# SSTuino_Evo.net
KiCad netlist of a schematic drawn in EAGLE
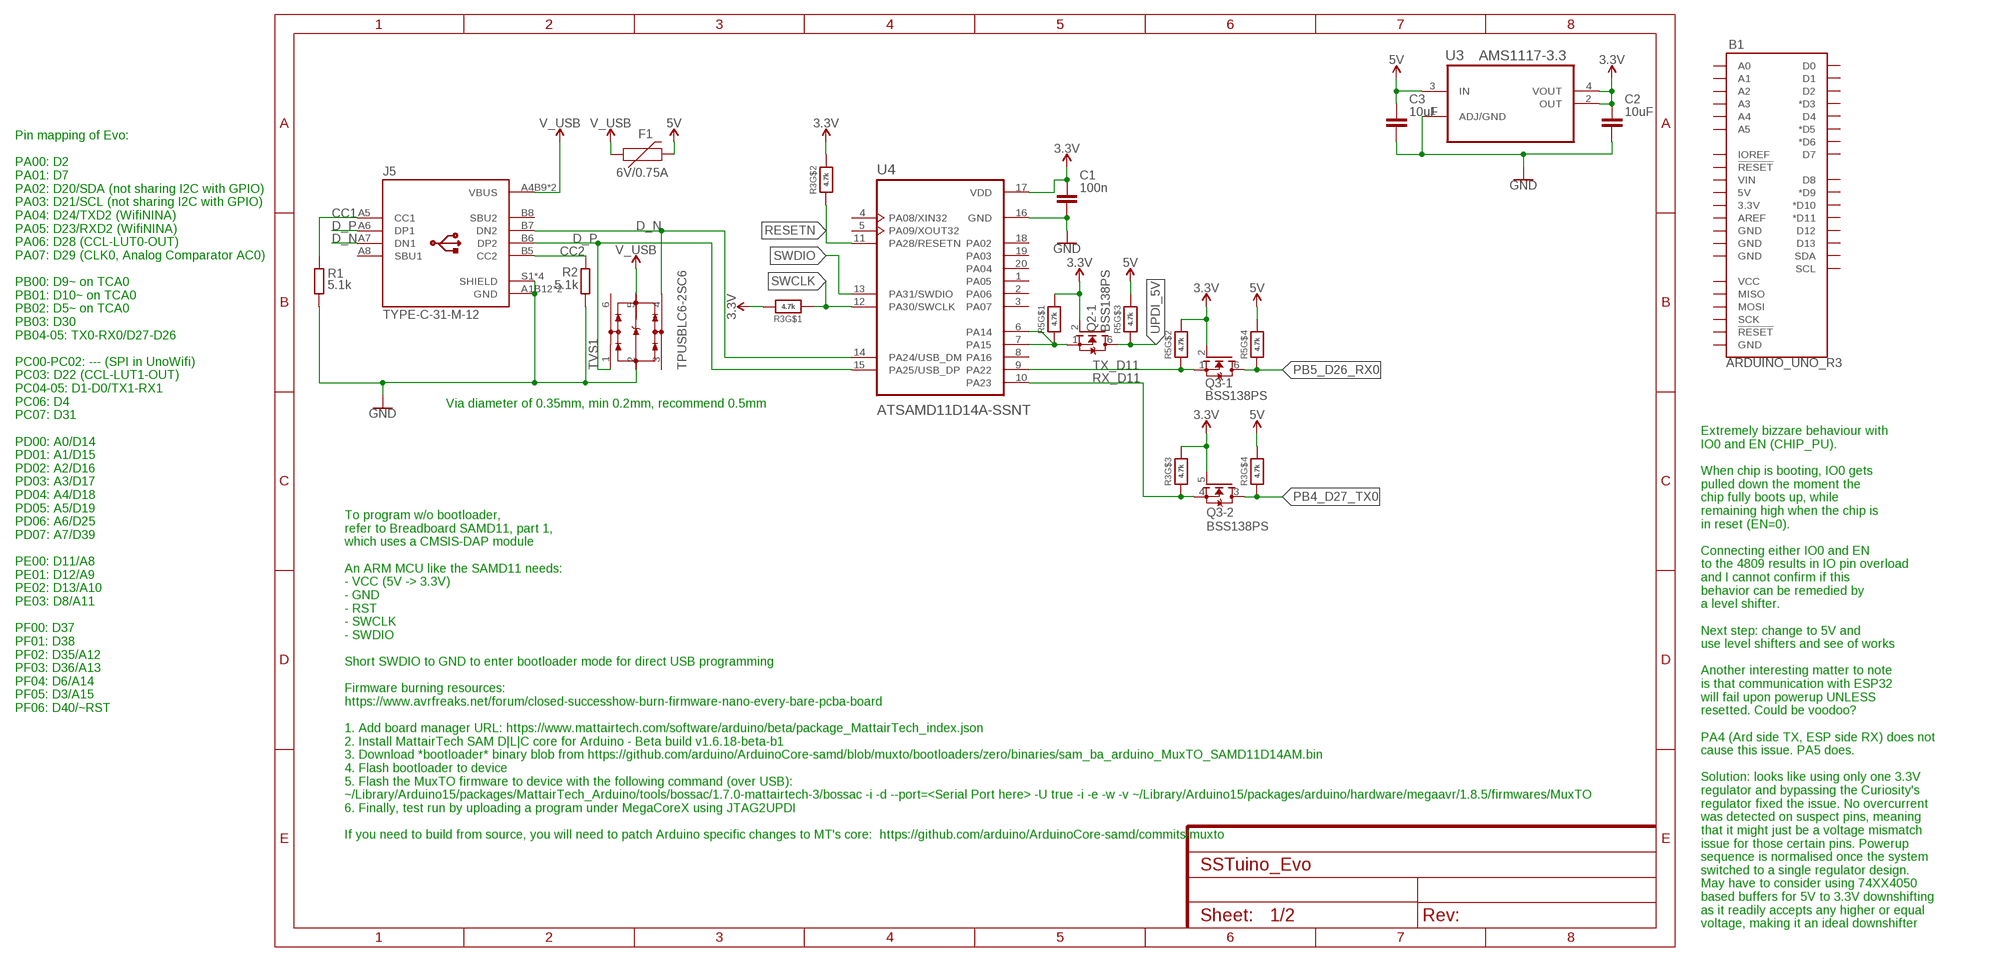
[diagram p0: schematic, sheet 1]
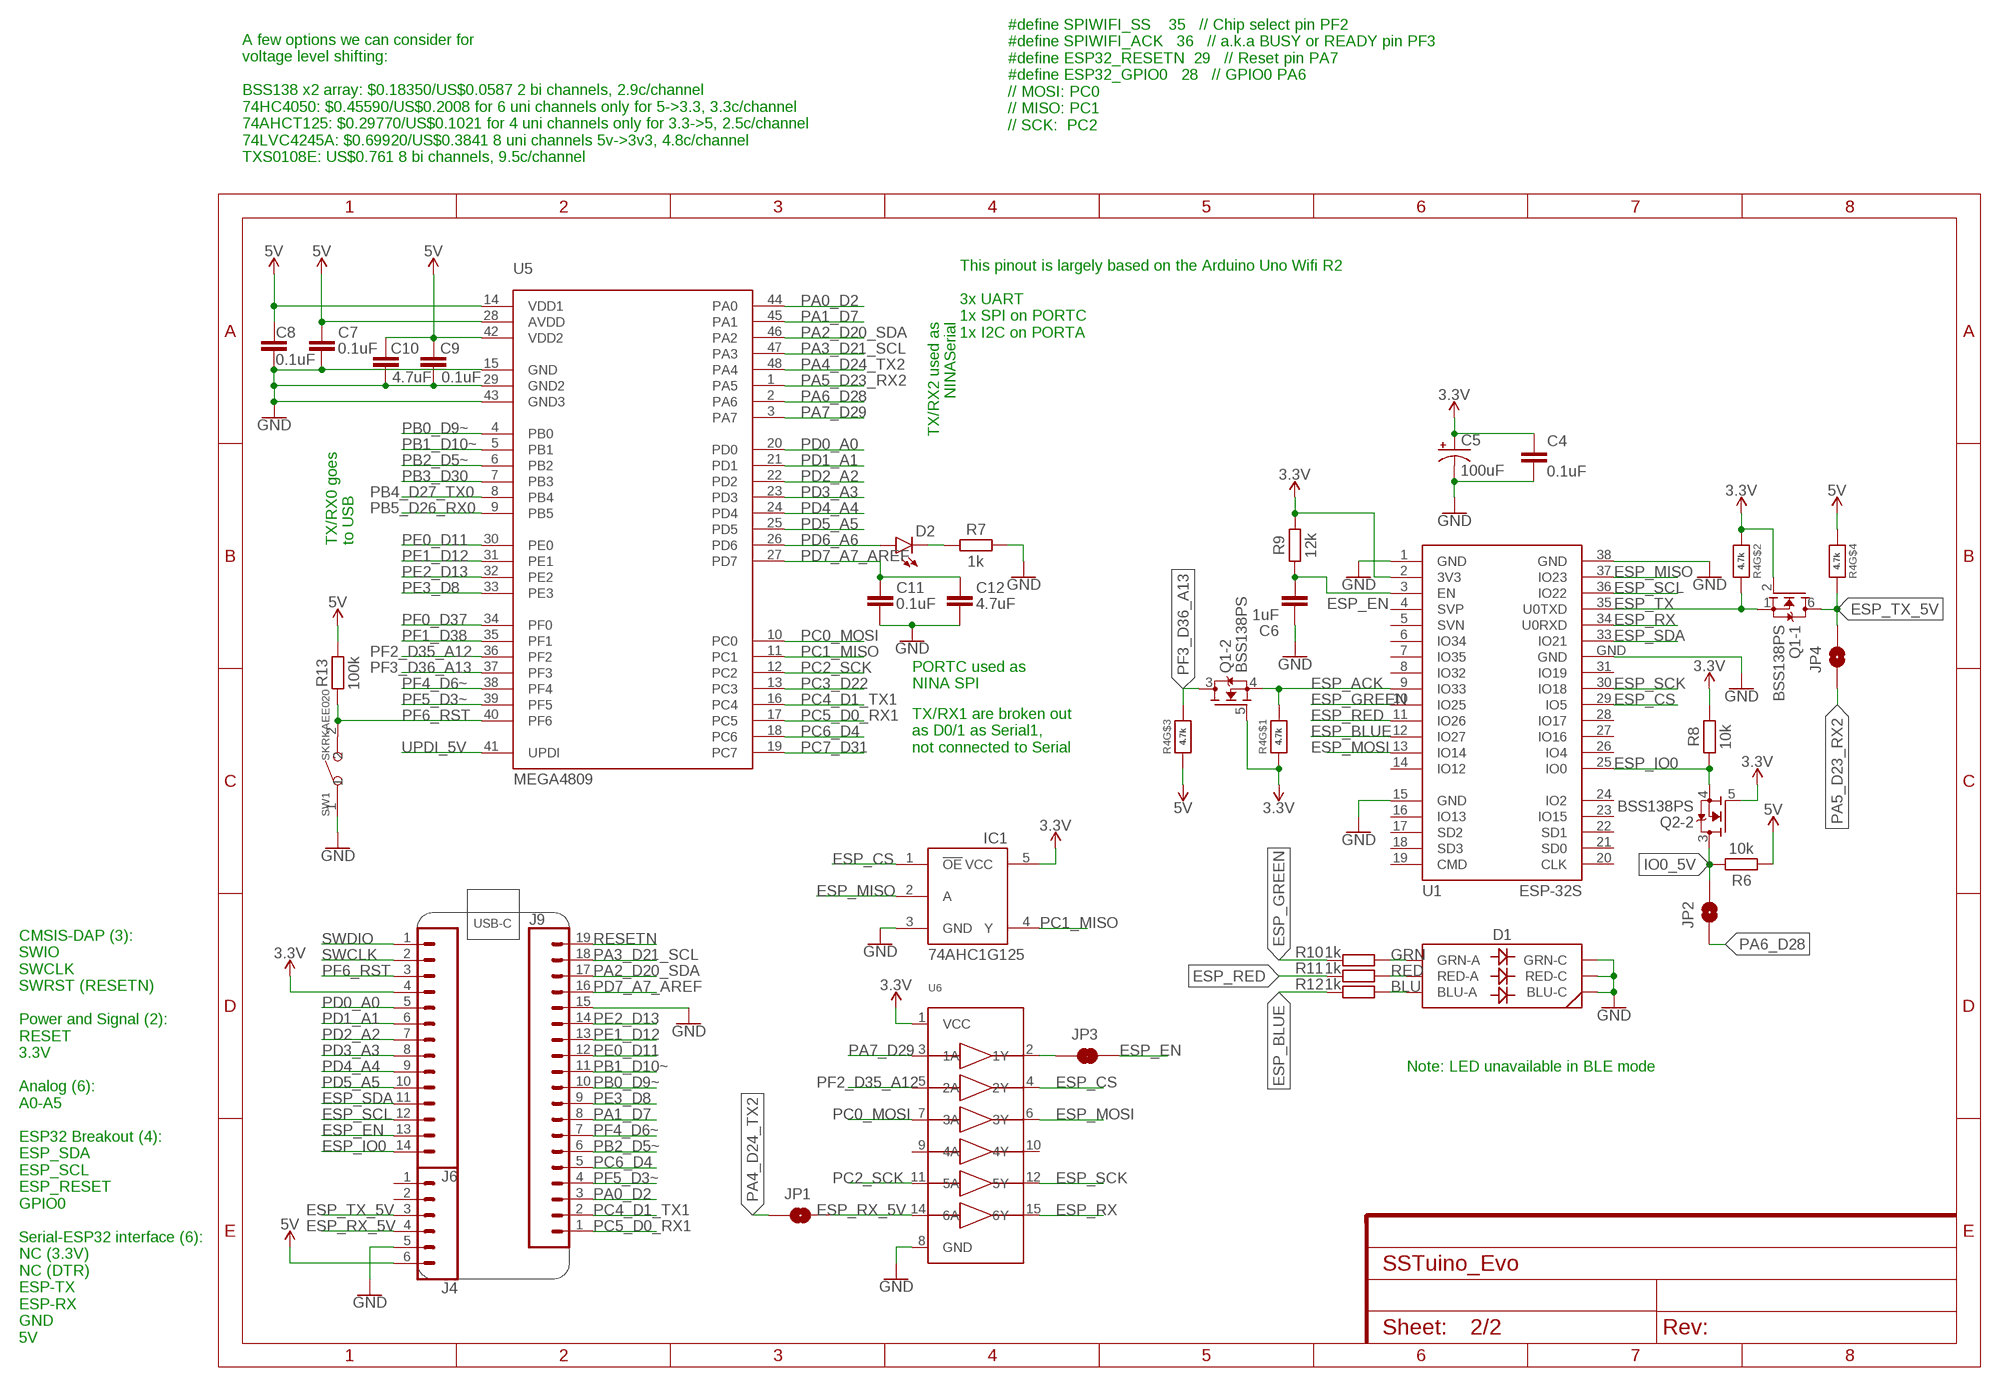
[diagram p1: schematic, sheet 2]

(export (version "E")
  (design (tool "Eeschema 10.0.6"))
  (components
    (comp (ref "B1")
      (value "ARDUINO_UNO_R3")
      (footprint "eagle-import:ARDUINO_R3")
      (libsource (lib "eagle-import") (part "ARDUINO_UNO_R3"))
    )
    (comp (ref "C1")
      (value "100n")
      (footprint "eagle-import:CAPC1005X60")
      (libsource (lib "eagle-import") (part "CCHIP-0402(1005-METRIC)_"))
    )
    (comp (ref "C2")
      (value "10uF")
      (footprint "eagle-import:CAPC1608X85")
      (libsource (lib "eagle-import") (part "CCHIP-0603(1608-METRIC)_"))
    )
    (comp (ref "C3")
      (value "10uF")
      (footprint "eagle-import:CAPC1608X85")
      (libsource (lib "eagle-import") (part "CCHIP-0603(1608-METRIC)_"))
    )
    (comp (ref "F1")
      (value "6V/0.75A")
      (footprint "eagle-import:1206")
      (fields (field (name "LCSC_PART") "C99563"))
      (libsource (lib "eagle-import") (part "PPTC_THREE-QUARTER-AMP"))
    )
    (comp (ref "J5")
      (value "TYPE-C-31-M-12")
      (footprint "eagle-import:HRO_TYPE-C-31-M-12")
      (fields (field (name "MF") "HRO Electronics Co., Ltd.") (field (name "LCSC_PART") "C165948"))
      (libsource (lib "eagle-import") (part "TYPE-C-31-M-12"))
    )
    (comp (ref "Q2")
      (value "BSS138PS")
      (footprint "eagle-import:ARDUINO-TRANSISTORS_SOT363")
      (fields (field (name "MANUFACTURER") "NXP") (field (name "LCSC_PART") "C193381"))
      (libsource (lib "eagle-import") (part "BSS138PS"))
    )
    (comp (ref "Q3")
      (value "BSS138PS")
      (footprint "eagle-import:ARDUINO-TRANSISTORS_SOT363")
      (fields (field (name "MANUFACTURER") "NXP") (field (name "LCSC_PART") "C193381"))
      (libsource (lib "eagle-import") (part "BSS138PS"))
    )
    (comp (ref "R1")
      (value "5.1k")
      (footprint "eagle-import:RESC1005X40")
      (libsource (lib "eagle-import") (part "RCHIP-0402(1005-METRIC)_"))
    )
    (comp (ref "R2")
      (value "5.1k")
      (footprint "eagle-import:RESC1005X40")
      (libsource (lib "eagle-import") (part "RCHIP-0402(1005-METRIC)_"))
    )
    (comp (ref "R3")
      (value "4.7k")
      (footprint "eagle-import:RESPACK_4X0402")
      (fields (field (name "LCSC_PART") "C1980"))
      (libsource (lib "eagle-import") (part "RESISTOR_4PACK0402"))
    )
    (comp (ref "R5")
      (value "4.7k")
      (footprint "eagle-import:RESPACK_4X0402")
      (fields (field (name "LCSC_PART") "C1980"))
      (libsource (lib "eagle-import") (part "RESISTOR_4PACK0402"))
    )
    (comp (ref "TVS1")
      (value "TPUSBLC6-2SC6")
      (footprint "eagle-import:SOT95P280X110-6N")
      (fields (field (name "LCSC_PART") "C558442"))
      (libsource (lib "eagle-import") (part "TPUSBLC6-2SC6"))
    )
    (comp (ref "U3")
      (value "AMS1117-3.3")
      (footprint "eagle-import:SOT230P696X180-4N")
      (fields (field (name "MPN") "LM1117MP-3.3") (field (name "LCSC_PART") "C6186"))
      (libsource (lib "eagle-import") (part "LM1117MP-3.3"))
    )
    (comp (ref "U4")
      (value "ATSAMD11D14A-SSNT")
      (footprint "eagle-import:SOIC127P1030X265-20N")
      (fields (field (name "MF") "Microchip") (field (name "LCSC_PART") "C2053599"))
      (libsource (lib "eagle-import") (part "ATSAMD11D14A-SSNT"))
    )
    (comp (ref "C4")
      (value "0.1uF")
      (footprint "eagle-import:CAPC1005X60")
      (libsource (lib "eagle-import") (part "CCHIP-0402(1005-METRIC)_"))
    )
    (comp (ref "C5")
      (value "100uF")
      (footprint "eagle-import:CAPMP3216X180N")
      (libsource (lib "eagle-import") (part "C-POL-USTANTALUM-1206(3216-METRIC)_"))
    )
    (comp (ref "C6")
      (value "1uF")
      (footprint "eagle-import:CAPC1005X60")
      (libsource (lib "eagle-import") (part "CCHIP-0402(1005-METRIC)_"))
    )
    (comp (ref "C7")
      (value "0.1uF")
      (footprint "eagle-import:CAPC1005X60")
      (libsource (lib "eagle-import") (part "CCHIP-0402(1005-METRIC)_"))
    )
    (comp (ref "C8")
      (value "0.1uF")
      (footprint "eagle-import:CAPC1005X60")
      (libsource (lib "eagle-import") (part "CCHIP-0402(1005-METRIC)_"))
    )
    (comp (ref "C9")
      (value "0.1uF")
      (footprint "eagle-import:CAPC1005X60")
      (libsource (lib "eagle-import") (part "CCHIP-0402(1005-METRIC)_"))
    )
    (comp (ref "C10")
      (value "4.7uF")
      (footprint "eagle-import:CAPC1005X60")
      (libsource (lib "eagle-import") (part "CCHIP-0402(1005-METRIC)_"))
    )
    (comp (ref "C11")
      (value "0.1uF")
      (footprint "eagle-import:CAPC1005X60")
      (libsource (lib "eagle-import") (part "CCHIP-0402(1005-METRIC)_"))
    )
    (comp (ref "C12")
      (value "4.7uF")
      (footprint "eagle-import:CAPC1005X60")
      (libsource (lib "eagle-import") (part "CCHIP-0402(1005-METRIC)_"))
    )
    (comp (ref "D1")
      (value "LED-RGBTC5050RGBF08")
      (footprint "eagle-import:LED-TRICOLOR-5050")
      (libsource (lib "eagle-import") (part "LED-RGBTC5050RGBF08"))
    )
    (comp (ref "D2")
      (value "LED0603")
      (footprint "eagle-import:LED-0603")
      (libsource (lib "eagle-import") (part "LED0603"))
    )
    (comp (ref "IC1")
      (value "74AHC1G125")
      (footprint "eagle-import:SOT23-5L")
      (fields (field (name "LCSC_PART") "C124295"))
      (libsource (lib "eagle-import") (part "74AHC1G125"))
    )
    (comp (ref "J4")
      (value "CONN_06NO_SILK_FEMALE_PTH")
      (footprint "eagle-import:1X06_NO_SILK")
      (libsource (lib "eagle-import") (part "CONN_06NO_SILK_FEMALE_PTH"))
    )
    (comp (ref "J6")
      (value "CONN_14NO_SILK")
      (footprint "eagle-import:1X14_NO_SILK")
      (libsource (lib "eagle-import") (part "CONN_14NO_SILK"))
    )
    (comp (ref "J9")
      (value "CONN_191X19_NO_SILK")
      (footprint "eagle-import:1X19_NO_SILK")
      (libsource (lib "eagle-import") (part "CONN_191X19_NO_SILK"))
    )
    (comp (ref "JP1")
      (value "JUMPER-SMT_2_NO_SILK")
      (footprint "eagle-import:SMT-JUMPER_2_NO_SILK")
      (libsource (lib "eagle-import") (part "JUMPER-SMT_2_NO_SILK"))
    )
    (comp (ref "JP2")
      (value "JUMPER-SMT_2_NO_SILK")
      (footprint "eagle-import:SMT-JUMPER_2_NO_SILK")
      (libsource (lib "eagle-import") (part "JUMPER-SMT_2_NO_SILK"))
    )
    (comp (ref "JP3")
      (value "JUMPER-SMT_2_NC_TRACE_SILK")
      (footprint "eagle-import:SMT-JUMPER_2_NC_TRACE_SILK")
      (libsource (lib "eagle-import") (part "JUMPER-SMT_2_NC_TRACE_SILK"))
    )
    (comp (ref "JP4")
      (value "JUMPER-SMT_2_NO_SILK")
      (footprint "eagle-import:SMT-JUMPER_2_NO_SILK")
      (libsource (lib "eagle-import") (part "JUMPER-SMT_2_NO_SILK"))
    )
    (comp (ref "Q1")
      (value "BSS138PS")
      (footprint "eagle-import:ARDUINO-TRANSISTORS_SOT363")
      (fields (field (name "MANUFACTURER") "NXP") (field (name "LCSC_PART") "C193381"))
      (libsource (lib "eagle-import") (part "BSS138PS"))
    )
    (comp (ref "R4")
      (value "4.7k")
      (footprint "eagle-import:RESPACK_4X0402")
      (fields (field (name "LCSC_PART") "C1980"))
      (libsource (lib "eagle-import") (part "RESISTOR_4PACK0402"))
    )
    (comp (ref "R6")
      (value "10k")
      (footprint "eagle-import:RESC1005X40")
      (libsource (lib "eagle-import") (part "RCHIP-0402(1005-METRIC)_"))
    )
    (comp (ref "R7")
      (value "1k")
      (footprint "eagle-import:RESC1005X40")
      (libsource (lib "eagle-import") (part "RCHIP-0402(1005-METRIC)_"))
    )
    (comp (ref "R8")
      (value "10k")
      (footprint "eagle-import:RESC1005X40")
      (libsource (lib "eagle-import") (part "RCHIP-0402(1005-METRIC)_"))
    )
    (comp (ref "R9")
      (value "12k")
      (footprint "eagle-import:RESC1005X40")
      (libsource (lib "eagle-import") (part "RCHIP-0402(1005-METRIC)_"))
    )
    (comp (ref "R10")
      (value "1k")
      (footprint "eagle-import:RESC1005X40")
      (libsource (lib "eagle-import") (part "RCHIP-0402(1005-METRIC)_"))
    )
    (comp (ref "R11")
      (value "1k")
      (footprint "eagle-import:RESC1005X40")
      (libsource (lib "eagle-import") (part "RCHIP-0402(1005-METRIC)_"))
    )
    (comp (ref "R12")
      (value "1k")
      (footprint "eagle-import:RESC1005X40")
      (libsource (lib "eagle-import") (part "RCHIP-0402(1005-METRIC)_"))
    )
    (comp (ref "R13")
      (value "100k")
      (footprint "eagle-import:RESC1005X40")
      (libsource (lib "eagle-import") (part "RCHIP-0402(1005-METRIC)_"))
    )
    (comp (ref "SW1")
      (value "SKRKAEE020")
      (footprint "eagle-import:SW2-2.6-3.9X2.9X1.5+0.4MM")
      (fields (field (name "LCSC_PART") "C115357") (field (name "LCSC_PART_1") "C115357"))
      (libsource (lib "eagle-import") (part "SMD-BUTTON(2P-3.9X2.9X1.5+0.4MM)-SKRKAEE020"))
    )
    (comp (ref "U1")
      (value "ESP-32S")
      (footprint "eagle-import:ESP-32S")
      (libsource (lib "eagle-import") (part "ESP-32S"))
    )
    (comp (ref "U5")
      (value "MEGA4809")
      (footprint "eagle-import:TQFP48")
      (fields (field (name "LCSC_PART") "C189475"))
      (libsource (lib "eagle-import") (part "MEGA4809"))
    )
    (comp (ref "U6")
      (value "74HC4050DTSSOP")
      (footprint "eagle-import:TSSOP16")
      (fields (field (name "LCSC_PART") "C43181"))
      (libsource (lib "eagle-import") (part "74HC4050DTSSOP"))
    )
  )
  (nets
    (net (code "1") (name "3.3V") (class "Default")
      (node (ref "C1") (pin "1") (pinfunction "1_1") (pintype "passive"))
      (node (ref "C2") (pin "1") (pinfunction "1_1") (pintype "passive"))
      (node (ref "C4") (pin "1") (pinfunction "1_1") (pintype "passive"))
      (node (ref "C5") (pin "1") (pinfunction "+_1") (pintype "passive"))
      (node (ref "IC1") (pin "5") (pinfunction "VCC_5") (pintype "power_in"))
      (node (ref "J6") (pin "4") (pinfunction "4_4") (pintype "passive"))
      (node (ref "Q1") (pin "2") (pinfunction "G_2") (pintype "passive"))
      (node (ref "Q1") (pin "5") (pinfunction "G_5") (pintype "passive"))
      (node (ref "Q2") (pin "2") (pinfunction "G_2") (pintype "passive"))
      (node (ref "Q2") (pin "5") (pinfunction "G_5") (pintype "passive"))
      (node (ref "Q3") (pin "2") (pinfunction "G_2") (pintype "passive"))
      (node (ref "Q3") (pin "5") (pinfunction "G_5") (pintype "passive"))
      (node (ref "R3") (pin "6") (pinfunction "2_6") (pintype "passive"))
      (node (ref "R3") (pin "7") (pinfunction "2_7") (pintype "passive"))
      (node (ref "R3") (pin "8") (pinfunction "2_8") (pintype "passive"))
      (node (ref "R4") (pin "1") (pinfunction "1_1") (pintype "passive"))
      (node (ref "R4") (pin "2") (pinfunction "1_2") (pintype "passive"))
      (node (ref "R5") (pin "7") (pinfunction "2_7") (pintype "passive"))
      (node (ref "R5") (pin "8") (pinfunction "2_8") (pintype "passive"))
      (node (ref "R8") (pin "2") (pinfunction "2_2") (pintype "passive"))
      (node (ref "R9") (pin "2") (pinfunction "2_2") (pintype "passive"))
      (node (ref "U1") (pin "2") (pinfunction "3V3_2") (pintype "power_in"))
      (node (ref "U3") (pin "2") (pinfunction "OUT_2") (pintype "output"))
      (node (ref "U3") (pin "4") (pinfunction "VOUT_4") (pintype "output"))
      (node (ref "U4") (pin "17") (pinfunction "VDD_17") (pintype "power_in"))
      (node (ref "U6") (pin "1") (pinfunction "VCC_1") (pintype "bidirectional"))
    )
    (net (code "2") (name "5V") (class "Default")
      (node (ref "C10") (pin "1") (pinfunction "1_1") (pintype "passive"))
      (node (ref "C3") (pin "1") (pinfunction "1_1") (pintype "passive"))
      (node (ref "C7") (pin "1") (pinfunction "1_1") (pintype "passive"))
      (node (ref "C8") (pin "1") (pinfunction "1_1") (pintype "passive"))
      (node (ref "C9") (pin "1") (pinfunction "1_1") (pintype "passive"))
      (node (ref "F1") (pin "2") (pinfunction "2_2") (pintype "bidirectional"))
      (node (ref "J4") (pin "6") (pinfunction "6_6") (pintype "passive"))
      (node (ref "R13") (pin "2") (pinfunction "2_2") (pintype "passive"))
      (node (ref "R3") (pin "5") (pinfunction "2_5") (pintype "passive"))
      (node (ref "R4") (pin "3") (pinfunction "1_3") (pintype "passive"))
      (node (ref "R4") (pin "4") (pinfunction "1_4") (pintype "passive"))
      (node (ref "R5") (pin "5") (pinfunction "2_5") (pintype "passive"))
      (node (ref "R5") (pin "6") (pinfunction "2_6") (pintype "passive"))
      (node (ref "R6") (pin "1") (pinfunction "1_1") (pintype "passive"))
      (node (ref "U3") (pin "3") (pinfunction "IN_3") (pintype "input"))
      (node (ref "U5") (pin "14") (pinfunction "VDD1_14") (pintype "bidirectional"))
      (node (ref "U5") (pin "28") (pinfunction "AVDD_28") (pintype "bidirectional"))
      (node (ref "U5") (pin "42") (pinfunction "VDD2_42") (pintype "bidirectional"))
    )
    (net (code "3") (name "BLU") (class "Default")
      (node (ref "D1") (pin "6") (pinfunction "BLU-A_6") (pintype "bidirectional"))
      (node (ref "R12") (pin "2") (pinfunction "2_2") (pintype "passive"))
    )
    (net (code "4") (name "CC1") (class "Default")
      (node (ref "J5") (pin "A5") (pinfunction "CC1_A5") (pintype "bidirectional"))
      (node (ref "R1") (pin "1") (pinfunction "1_1") (pintype "passive"))
    )
    (net (code "5") (name "CC2") (class "Default")
      (node (ref "J5") (pin "B5") (pinfunction "CC2_B5") (pintype "bidirectional"))
      (node (ref "R2") (pin "2") (pinfunction "2_2") (pintype "passive"))
    )
    (net (code "6") (name "D_N") (class "Default")
      (node (ref "J5") (pin "A7") (pinfunction "DN1_A7") (pintype "bidirectional"))
      (node (ref "J5") (pin "B7") (pinfunction "DN2_B7") (pintype "bidirectional"))
      (node (ref "TVS1") (pin "4") (pinfunction "IO3_4") (pintype "passive"))
      (node (ref "U4") (pin "14") (pinfunction "PA24/USB_DM_14") (pintype "bidirectional"))
    )
    (net (code "7") (name "D_P") (class "Default")
      (node (ref "J5") (pin "A6") (pinfunction "DP1_A6") (pintype "bidirectional"))
      (node (ref "J5") (pin "B6") (pinfunction "DP2_B6") (pintype "bidirectional"))
      (node (ref "TVS1") (pin "1") (pinfunction "IO1_1") (pintype "passive"))
      (node (ref "U4") (pin "15") (pinfunction "PA25/USB_DP_15") (pintype "bidirectional"))
    )
    (net (code "8") (name "ESP_ACK") (class "Default")
      (node (ref "Q1") (pin "4") (pinfunction "S_4") (pintype "passive"))
      (node (ref "R4") (pin "8") (pinfunction "2_8") (pintype "passive"))
      (node (ref "U1") (pin "9") (pinfunction "IO33_9") (pintype "bidirectional"))
    )
    (net (code "9") (name "ESP_BLUE") (class "Default")
      (node (ref "R12") (pin "1") (pinfunction "1_1") (pintype "passive"))
      (node (ref "U1") (pin "12") (pinfunction "IO27_12") (pintype "bidirectional"))
    )
    (net (code "10") (name "ESP_CS") (class "Default")
      (node (ref "IC1") (pin "1") (pinfunction "~{OE}_1") (pintype "input"))
      (node (ref "U1") (pin "29") (pinfunction "IO5_29") (pintype "bidirectional"))
      (node (ref "U6") (pin "4") (pinfunction "2Y_4") (pintype "bidirectional"))
    )
    (net (code "11") (name "ESP_EN") (class "Default")
      (node (ref "C6") (pin "2") (pinfunction "2_2") (pintype "passive"))
      (node (ref "J6") (pin "13") (pinfunction "13_13") (pintype "passive"))
      (node (ref "JP3") (pin "2") (pinfunction "2_2") (pintype "passive"))
      (node (ref "R9") (pin "1") (pinfunction "1_1") (pintype "passive"))
      (node (ref "U1") (pin "3") (pinfunction "EN_3") (pintype "input"))
    )
    (net (code "12") (name "ESP_GREEN") (class "Default")
      (node (ref "R10") (pin "1") (pinfunction "1_1") (pintype "passive"))
      (node (ref "U1") (pin "10") (pinfunction "IO25_10") (pintype "bidirectional"))
    )
    (net (code "13") (name "ESP_IO0") (class "Default")
      (node (ref "J6") (pin "14") (pinfunction "14_14") (pintype "passive"))
      (node (ref "Q2") (pin "4") (pinfunction "S_4") (pintype "passive"))
      (node (ref "R8") (pin "1") (pinfunction "1_1") (pintype "passive"))
      (node (ref "U1") (pin "25") (pinfunction "IO0_25") (pintype "bidirectional"))
    )
    (net (code "14") (name "ESP_MISO") (class "Default")
      (node (ref "IC1") (pin "2") (pinfunction "A_2") (pintype "input"))
      (node (ref "U1") (pin "37") (pinfunction "IO23_37") (pintype "bidirectional"))
    )
    (net (code "15") (name "ESP_MOSI") (class "Default")
      (node (ref "U1") (pin "13") (pinfunction "IO14_13") (pintype "bidirectional"))
      (node (ref "U6") (pin "6") (pinfunction "3Y_6") (pintype "bidirectional"))
    )
    (net (code "16") (name "ESP_RED") (class "Default")
      (node (ref "R11") (pin "1") (pinfunction "1_1") (pintype "passive"))
      (node (ref "U1") (pin "11") (pinfunction "IO26_11") (pintype "bidirectional"))
    )
    (net (code "17") (name "ESP_RX") (class "Default")
      (node (ref "U1") (pin "34") (pinfunction "U0RXD_34") (pintype "bidirectional"))
      (node (ref "U6") (pin "15") (pinfunction "6Y_15") (pintype "bidirectional"))
    )
    (net (code "18") (name "ESP_RX_5V") (class "Default")
      (node (ref "J4") (pin "4") (pinfunction "4_4") (pintype "passive"))
      (node (ref "JP1") (pin "2") (pinfunction "2_2") (pintype "passive"))
      (node (ref "U6") (pin "14") (pinfunction "6A_14") (pintype "bidirectional"))
    )
    (net (code "19") (name "ESP_SCK") (class "Default")
      (node (ref "U1") (pin "30") (pinfunction "IO18_30") (pintype "bidirectional"))
      (node (ref "U6") (pin "12") (pinfunction "5Y_12") (pintype "bidirectional"))
    )
    (net (code "20") (name "ESP_SCL") (class "Default")
      (node (ref "J6") (pin "12") (pinfunction "12_12") (pintype "passive"))
      (node (ref "U1") (pin "36") (pinfunction "IO22_36") (pintype "bidirectional"))
    )
    (net (code "21") (name "ESP_SDA") (class "Default")
      (node (ref "J6") (pin "11") (pinfunction "11_11") (pintype "passive"))
      (node (ref "U1") (pin "33") (pinfunction "IO21_33") (pintype "bidirectional"))
    )
    (net (code "22") (name "ESP_TX") (class "Default")
      (node (ref "Q1") (pin "1") (pinfunction "S_1") (pintype "passive"))
      (node (ref "R4") (pin "7") (pinfunction "2_7") (pintype "passive"))
      (node (ref "U1") (pin "35") (pinfunction "U0TXD_35") (pintype "bidirectional"))
    )
    (net (code "23") (name "ESP_TX_5V") (class "Default")
      (node (ref "J4") (pin "3") (pinfunction "3_3") (pintype "passive"))
      (node (ref "JP4") (pin "2") (pinfunction "2_2") (pintype "passive"))
      (node (ref "Q1") (pin "6") (pinfunction "D_6") (pintype "passive"))
      (node (ref "R4") (pin "5") (pinfunction "2_5") (pintype "passive"))
    )
    (net (code "24") (name "GND") (class "Default")
      (node (ref "C1") (pin "2") (pinfunction "2_2") (pintype "passive"))
      (node (ref "C10") (pin "2") (pinfunction "2_2") (pintype "passive"))
      (node (ref "C11") (pin "2") (pinfunction "2_2") (pintype "passive"))
      (node (ref "C12") (pin "2") (pinfunction "2_2") (pintype "passive"))
      (node (ref "C2") (pin "2") (pinfunction "2_2") (pintype "passive"))
      (node (ref "C3") (pin "2") (pinfunction "2_2") (pintype "passive"))
      (node (ref "C4") (pin "2") (pinfunction "2_2") (pintype "passive"))
      (node (ref "C5") (pin "2") (pinfunction "-_2") (pintype "passive"))
      (node (ref "C6") (pin "1") (pinfunction "1_1") (pintype "passive"))
      (node (ref "C7") (pin "2") (pinfunction "2_2") (pintype "passive"))
      (node (ref "C8") (pin "2") (pinfunction "2_2") (pintype "passive"))
      (node (ref "C9") (pin "2") (pinfunction "2_2") (pintype "passive"))
      (node (ref "D1") (pin "1") (pinfunction "BLU-C_1") (pintype "bidirectional"))
      (node (ref "D1") (pin "2") (pinfunction "RED-C_2") (pintype "bidirectional"))
      (node (ref "D1") (pin "3") (pinfunction "GRN-C_3") (pintype "bidirectional"))
      (node (ref "IC1") (pin "3") (pinfunction "GND_3") (pintype "power_in"))
      (node (ref "J4") (pin "5") (pinfunction "5_5") (pintype "passive"))
      (node (ref "J5") (pin "A1B12") (pinfunction "GND_A1B12") (pintype "power_in"))
      (node (ref "J5") (pin "B1A12") (pinfunction "GND_B1A12") (pintype "power_in"))
      (node (ref "J5") (pin "S1") (pinfunction "SHIELD_S1") (pintype "passive"))
      (node (ref "J5") (pin "S2") (pinfunction "SHIELD_S2") (pintype "passive"))
      (node (ref "J5") (pin "S3") (pinfunction "SHIELD_S3") (pintype "passive"))
      (node (ref "J5") (pin "S4") (pinfunction "SHIELD_S4") (pintype "passive"))
      (node (ref "J9") (pin "15") (pinfunction "15_15") (pintype "passive"))
      (node (ref "R1") (pin "2") (pinfunction "2_2") (pintype "passive"))
      (node (ref "R2") (pin "1") (pinfunction "1_1") (pintype "passive"))
      (node (ref "R7") (pin "2") (pinfunction "2_2") (pintype "passive"))
      (node (ref "SW1") (pin "1") (pinfunction "1_1") (pintype "bidirectional"))
      (node (ref "TVS1") (pin "2") (pinfunction "VSS_2") (pintype "power_in"))
      (node (ref "U1") (pin "1") (pinfunction "GND_1") (pintype "power_in"))
      (node (ref "U1") (pin "15") (pinfunction "GND_15") (pintype "power_in"))
      (node (ref "U1") (pin "38") (pinfunction "GND_38") (pintype "power_in"))
      (node (ref "U1") (pin "GND") (pinfunction "GND_GND") (pintype "power_in"))
      (node (ref "U3") (pin "1") (pinfunction "ADJ/GND_1") (pintype "passive"))
      (node (ref "U4") (pin "16") (pinfunction "GND_16") (pintype "power_in"))
      (node (ref "U5") (pin "15") (pinfunction "GND_15") (pintype "bidirectional"))
      (node (ref "U5") (pin "29") (pinfunction "GND2_29") (pintype "bidirectional"))
      (node (ref "U5") (pin "43") (pinfunction "GND3_43") (pintype "bidirectional"))
      (node (ref "U6") (pin "8") (pinfunction "GND_8") (pintype "bidirectional"))
    )
    (net (code "25") (name "GRN") (class "Default")
      (node (ref "D1") (pin "4") (pinfunction "GRN-A_4") (pintype "bidirectional"))
      (node (ref "R10") (pin "2") (pinfunction "2_2") (pintype "passive"))
    )
    (net (code "26") (name "IO0_5V") (class "Default")
      (node (ref "JP2") (pin "2") (pinfunction "2_2") (pintype "passive"))
      (node (ref "Q2") (pin "3") (pinfunction "D_3") (pintype "passive"))
      (node (ref "R6") (pin "2") (pinfunction "2_2") (pintype "passive"))
    )
    (net (code "27") (name "Net-(D2-PadC)") (class "Default")
      (node (ref "D2") (pin "C") (pinfunction "C_C") (pintype "passive"))
      (node (ref "R7") (pin "1") (pinfunction "1_1") (pintype "passive"))
    )
    (net (code "28") (name "Net-(Q2A-S)") (class "Default")
      (node (ref "Q2") (pin "1") (pinfunction "S_1") (pintype "passive"))
      (node (ref "R5") (pin "1") (pinfunction "1_1") (pintype "passive"))
      (node (ref "U4") (pin "6") (pinfunction "PA14_6") (pintype "bidirectional"))
      (node (ref "U4") (pin "7") (pinfunction "PA15_7") (pintype "bidirectional"))
    )
    (net (code "29") (name "Net-(U6-1Y)") (class "Default")
      (node (ref "JP3") (pin "1") (pinfunction "1_1") (pintype "passive"))
      (node (ref "U6") (pin "2") (pinfunction "1Y_2") (pintype "bidirectional"))
    )
    (net (code "30") (name "PA0_D2") (class "Default")
      (node (ref "J9") (pin "3") (pinfunction "3_3") (pintype "passive"))
      (node (ref "U5") (pin "44") (pinfunction "PA0_44") (pintype "bidirectional"))
    )
    (net (code "31") (name "PA1_D7") (class "Default")
      (node (ref "J9") (pin "8") (pinfunction "8_8") (pintype "passive"))
      (node (ref "U5") (pin "45") (pinfunction "PA1_45") (pintype "bidirectional"))
    )
    (net (code "32") (name "PA2_D20_SDA") (class "Default")
      (node (ref "J9") (pin "17") (pinfunction "17_17") (pintype "passive"))
      (node (ref "U5") (pin "46") (pinfunction "PA2_46") (pintype "bidirectional"))
    )
    (net (code "33") (name "PA3_D21_SCL") (class "Default")
      (node (ref "J9") (pin "18") (pinfunction "18_18") (pintype "passive"))
      (node (ref "U5") (pin "47") (pinfunction "PA3_47") (pintype "bidirectional"))
    )
    (net (code "34") (name "PA4_D24_TX2") (class "Default")
      (node (ref "JP1") (pin "1") (pinfunction "1_1") (pintype "passive"))
      (node (ref "U5") (pin "48") (pinfunction "PA4_48") (pintype "bidirectional"))
    )
    (net (code "35") (name "PA5_D23_RX2") (class "Default")
      (node (ref "JP4") (pin "1") (pinfunction "1_1") (pintype "passive"))
      (node (ref "U5") (pin "1") (pinfunction "PA5_1") (pintype "bidirectional"))
    )
    (net (code "36") (name "PA6_D28") (class "Default")
      (node (ref "JP2") (pin "1") (pinfunction "1_1") (pintype "passive"))
      (node (ref "U5") (pin "2") (pinfunction "PA6_2") (pintype "bidirectional"))
    )
    (net (code "37") (name "PA7_D29") (class "Default")
      (node (ref "U5") (pin "3") (pinfunction "PA7_3") (pintype "bidirectional"))
      (node (ref "U6") (pin "3") (pinfunction "1A_3") (pintype "bidirectional"))
    )
    (net (code "38") (name "PB0_D9~{}") (class "Default")
      (node (ref "J9") (pin "10") (pinfunction "10_10") (pintype "passive"))
      (node (ref "U5") (pin "4") (pinfunction "PB0_4") (pintype "bidirectional"))
    )
    (net (code "39") (name "PB1_D10~{}") (class "Default")
      (node (ref "J9") (pin "11") (pinfunction "11_11") (pintype "passive"))
      (node (ref "U5") (pin "5") (pinfunction "PB1_5") (pintype "bidirectional"))
    )
    (net (code "40") (name "PB2_D5~{}") (class "Default")
      (node (ref "J9") (pin "6") (pinfunction "6_6") (pintype "passive"))
      (node (ref "U5") (pin "6") (pinfunction "PB2_6") (pintype "bidirectional"))
    )
    (net (code "41") (name "PB3_D30") (class "Default")
      (node (ref "U5") (pin "7") (pinfunction "PB3_7") (pintype "bidirectional"))
    )
    (net (code "42") (name "PB4_D27_TX0") (class "Default")
      (node (ref "Q3") (pin "3") (pinfunction "D_3") (pintype "passive"))
      (node (ref "R3") (pin "4") (pinfunction "1_4") (pintype "passive"))
      (node (ref "U5") (pin "8") (pinfunction "PB4_8") (pintype "bidirectional"))
    )
    (net (code "43") (name "PB5_D26_RX0") (class "Default")
      (node (ref "Q3") (pin "6") (pinfunction "D_6") (pintype "passive"))
      (node (ref "R5") (pin "4") (pinfunction "1_4") (pintype "passive"))
      (node (ref "U5") (pin "9") (pinfunction "PB5_9") (pintype "bidirectional"))
    )
    (net (code "44") (name "PC0_MOSI") (class "Default")
      (node (ref "U5") (pin "10") (pinfunction "PC0_10") (pintype "bidirectional"))
      (node (ref "U6") (pin "7") (pinfunction "3A_7") (pintype "bidirectional"))
    )
    (net (code "45") (name "PC1_MISO") (class "Default")
      (node (ref "IC1") (pin "4") (pinfunction "Y_4") (pintype "output"))
      (node (ref "U5") (pin "11") (pinfunction "PC1_11") (pintype "bidirectional"))
    )
    (net (code "46") (name "PC2_SCK") (class "Default")
      (node (ref "U5") (pin "12") (pinfunction "PC2_12") (pintype "bidirectional"))
      (node (ref "U6") (pin "11") (pinfunction "5A_11") (pintype "bidirectional"))
    )
    (net (code "47") (name "PC3_D22") (class "Default")
      (node (ref "U5") (pin "13") (pinfunction "PC3_13") (pintype "bidirectional"))
    )
    (net (code "48") (name "PC4_D1_TX1") (class "Default")
      (node (ref "J9") (pin "2") (pinfunction "2_2") (pintype "passive"))
      (node (ref "U5") (pin "16") (pinfunction "PC4_16") (pintype "bidirectional"))
    )
    (net (code "49") (name "PC5_D0_RX1") (class "Default")
      (node (ref "J9") (pin "1") (pinfunction "1_1") (pintype "passive"))
      (node (ref "U5") (pin "17") (pinfunction "PC5_17") (pintype "bidirectional"))
    )
    (net (code "50") (name "PC6_D4") (class "Default")
      (node (ref "J9") (pin "5") (pinfunction "5_5") (pintype "passive"))
      (node (ref "U5") (pin "18") (pinfunction "PC6_18") (pintype "bidirectional"))
    )
    (net (code "51") (name "PC7_D31") (class "Default")
      (node (ref "U5") (pin "19") (pinfunction "PC7_19") (pintype "bidirectional"))
    )
    (net (code "52") (name "PD0_A0") (class "Default")
      (node (ref "J6") (pin "5") (pinfunction "5_5") (pintype "passive"))
      (node (ref "U5") (pin "20") (pinfunction "PD0_20") (pintype "bidirectional"))
    )
    (net (code "53") (name "PD1_A1") (class "Default")
      (node (ref "J6") (pin "6") (pinfunction "6_6") (pintype "passive"))
      (node (ref "U5") (pin "21") (pinfunction "PD1_21") (pintype "bidirectional"))
    )
    (net (code "54") (name "PD2_A2") (class "Default")
      (node (ref "J6") (pin "7") (pinfunction "7_7") (pintype "passive"))
      (node (ref "U5") (pin "22") (pinfunction "PD2_22") (pintype "bidirectional"))
    )
    (net (code "55") (name "PD3_A3") (class "Default")
      (node (ref "J6") (pin "8") (pinfunction "8_8") (pintype "passive"))
      (node (ref "U5") (pin "23") (pinfunction "PD3_23") (pintype "bidirectional"))
    )
    (net (code "56") (name "PD4_A4") (class "Default")
      (node (ref "J6") (pin "9") (pinfunction "9_9") (pintype "passive"))
      (node (ref "U5") (pin "24") (pinfunction "PD4_24") (pintype "bidirectional"))
    )
    (net (code "57") (name "PD5_A5") (class "Default")
      (node (ref "J6") (pin "10") (pinfunction "10_10") (pintype "passive"))
      (node (ref "U5") (pin "25") (pinfunction "PD5_25") (pintype "bidirectional"))
    )
    (net (code "58") (name "PD6_A6") (class "Default")
      (node (ref "D2") (pin "A") (pinfunction "A_A") (pintype "passive"))
      (node (ref "U5") (pin "26") (pinfunction "PD6_26") (pintype "bidirectional"))
    )
    (net (code "59") (name "PD7_A7_AREF") (class "Default")
      (node (ref "C11") (pin "1") (pinfunction "1_1") (pintype "passive"))
      (node (ref "C12") (pin "1") (pinfunction "1_1") (pintype "passive"))
      (node (ref "J9") (pin "16") (pinfunction "16_16") (pintype "passive"))
      (node (ref "U5") (pin "27") (pinfunction "PD7_27") (pintype "bidirectional"))
    )
    (net (code "60") (name "PE0_D11") (class "Default")
      (node (ref "J9") (pin "12") (pinfunction "12_12") (pintype "passive"))
      (node (ref "U5") (pin "30") (pinfunction "PE0_30") (pintype "bidirectional"))
    )
    (net (code "61") (name "PE1_D12") (class "Default")
      (node (ref "J9") (pin "13") (pinfunction "13_13") (pintype "passive"))
      (node (ref "U5") (pin "31") (pinfunction "PE1_31") (pintype "bidirectional"))
    )
    (net (code "62") (name "PE2_D13") (class "Default")
      (node (ref "J9") (pin "14") (pinfunction "14_14") (pintype "passive"))
      (node (ref "U5") (pin "32") (pinfunction "PE2_32") (pintype "bidirectional"))
    )
    (net (code "63") (name "PE3_D8") (class "Default")
      (node (ref "J9") (pin "9") (pinfunction "9_9") (pintype "passive"))
      (node (ref "U5") (pin "33") (pinfunction "PE3_33") (pintype "bidirectional"))
    )
    (net (code "64") (name "PF0_D37") (class "Default")
      (node (ref "U5") (pin "34") (pinfunction "PF0_34") (pintype "bidirectional"))
    )
    (net (code "65") (name "PF1_D38") (class "Default")
      (node (ref "U5") (pin "35") (pinfunction "PF1_35") (pintype "bidirectional"))
    )
    (net (code "66") (name "PF2_D35_A12") (class "Default")
      (node (ref "U5") (pin "36") (pinfunction "PF2_36") (pintype "bidirectional"))
      (node (ref "U6") (pin "5") (pinfunction "2A_5") (pintype "bidirectional"))
    )
    (net (code "67") (name "PF3_D36_A13") (class "Default")
      (node (ref "Q1") (pin "3") (pinfunction "D_3") (pintype "passive"))
      (node (ref "R4") (pin "6") (pinfunction "2_6") (pintype "passive"))
      (node (ref "U5") (pin "37") (pinfunction "PF3_37") (pintype "bidirectional"))
    )
    (net (code "68") (name "PF4_D6~{}") (class "Default")
      (node (ref "J9") (pin "7") (pinfunction "7_7") (pintype "passive"))
      (node (ref "U5") (pin "38") (pinfunction "PF4_38") (pintype "bidirectional"))
    )
    (net (code "69") (name "PF5_D3~{}") (class "Default")
      (node (ref "J9") (pin "4") (pinfunction "4_4") (pintype "passive"))
      (node (ref "U5") (pin "39") (pinfunction "PF5_39") (pintype "bidirectional"))
    )
    (net (code "70") (name "PF6_RST") (class "Default")
      (node (ref "J6") (pin "3") (pinfunction "3_3") (pintype "passive"))
      (node (ref "R13") (pin "1") (pinfunction "1_1") (pintype "passive"))
      (node (ref "SW1") (pin "2") (pinfunction "2_2") (pintype "bidirectional"))
      (node (ref "U5") (pin "40") (pinfunction "PF6_40") (pintype "bidirectional"))
    )
    (net (code "71") (name "RED") (class "Default")
      (node (ref "D1") (pin "5") (pinfunction "RED-A_5") (pintype "bidirectional"))
      (node (ref "R11") (pin "2") (pinfunction "2_2") (pintype "passive"))
    )
    (net (code "72") (name "RESETN") (class "Default")
      (node (ref "J9") (pin "19") (pinfunction "19_19") (pintype "passive"))
      (node (ref "R3") (pin "2") (pinfunction "1_2") (pintype "passive"))
      (node (ref "U4") (pin "11") (pinfunction "PA28/RESETN_11") (pintype "input"))
    )
    (net (code "73") (name "RX_D11") (class "Default")
      (node (ref "Q3") (pin "4") (pinfunction "S_4") (pintype "passive"))
      (node (ref "R3") (pin "3") (pinfunction "1_3") (pintype "passive"))
      (node (ref "U4") (pin "10") (pinfunction "PA23_10") (pintype "bidirectional"))
    )
    (net (code "74") (name "SWCLK") (class "Default")
      (node (ref "J6") (pin "2") (pinfunction "2_2") (pintype "passive"))
      (node (ref "R3") (pin "1") (pinfunction "1_1") (pintype "passive"))
      (node (ref "U4") (pin "12") (pinfunction "PA30/SWCLK_12") (pintype "bidirectional"))
    )
    (net (code "75") (name "SWDIO") (class "Default")
      (node (ref "J6") (pin "1") (pinfunction "1_1") (pintype "passive"))
      (node (ref "U4") (pin "13") (pinfunction "PA31/SWDIO_13") (pintype "bidirectional"))
    )
    (net (code "76") (name "TX_D11") (class "Default")
      (node (ref "Q3") (pin "1") (pinfunction "S_1") (pintype "passive"))
      (node (ref "R5") (pin "2") (pinfunction "1_2") (pintype "passive"))
      (node (ref "U4") (pin "9") (pinfunction "PA22_9") (pintype "bidirectional"))
    )
    (net (code "77") (name "UPDI_5V") (class "Default")
      (node (ref "Q2") (pin "6") (pinfunction "D_6") (pintype "passive"))
      (node (ref "R5") (pin "3") (pinfunction "1_3") (pintype "passive"))
      (node (ref "U5") (pin "41") (pinfunction "UPDI_41") (pintype "bidirectional"))
    )
    (net (code "78") (name "V_USB") (class "Default")
      (node (ref "F1") (pin "1") (pinfunction "1_1") (pintype "bidirectional"))
      (node (ref "J5") (pin "A4B9") (pinfunction "VBUS_A4B9") (pintype "power_in"))
      (node (ref "J5") (pin "B4A9") (pinfunction "VBUS_B4A9") (pintype "power_in"))
      (node (ref "TVS1") (pin "5") (pinfunction "VCC_5") (pintype "power_in"))
    )
    (net (code "79") (name "unconnected-(B1-*D3-PadD3)") (class "Default")
      (node (ref "B1") (pin "D3") (pinfunction "*D3_D3") (pintype "bidirectional"))
    )
    (net (code "80") (name "unconnected-(B1-*D5-PadD5)") (class "Default")
      (node (ref "B1") (pin "D5") (pinfunction "*D5_D5") (pintype "bidirectional"))
    )
    (net (code "81") (name "unconnected-(B1-*D6-PadD6)") (class "Default")
      (node (ref "B1") (pin "D6") (pinfunction "*D6_D6") (pintype "bidirectional"))
    )
    (net (code "82") (name "unconnected-(B1-*D9-PadD9)") (class "Default")
      (node (ref "B1") (pin "D9") (pinfunction "*D9_D9") (pintype "bidirectional"))
    )
    (net (code "83") (name "unconnected-(B1-*D10-PadD10)") (class "Default")
      (node (ref "B1") (pin "D10") (pinfunction "*D10_D10") (pintype "bidirectional"))
    )
    (net (code "84") (name "unconnected-(B1-*D11-PadD11)") (class "Default")
      (node (ref "B1") (pin "D11") (pinfunction "*D11_D11") (pintype "bidirectional"))
    )
    (net (code "85") (name "unconnected-(B1-GND-PadGND@1)") (class "Default")
      (node (ref "B1") (pin "GND@1") (pinfunction "GND_GND@1") (pintype "bidirectional"))
    )
    (net (code "86") (name "unconnected-(B1-GND-PadGND@2)") (class "Default")
      (node (ref "B1") (pin "GND@2") (pinfunction "GND_GND@2") (pintype "bidirectional"))
    )
    (net (code "87") (name "unconnected-(B1-GND-PadGND@3)") (class "Default")
      (node (ref "B1") (pin "GND@3") (pinfunction "GND_GND@3") (pintype "bidirectional"))
    )
    (net (code "88") (name "unconnected-(B1-GND-PadGND@4)") (class "Default")
      (node (ref "B1") (pin "GND@4") (pinfunction "GND_GND@4") (pintype "bidirectional"))
    )
    (net (code "89") (name "unconnected-(B1-Pad3.3V)") (class "Default")
      (node (ref "B1") (pin "3.3V") (pinfunction "3.3V_3.3V") (pintype "bidirectional"))
    )
    (net (code "90") (name "unconnected-(B1-Pad5V)") (class "Default")
      (node (ref "B1") (pin "5V") (pinfunction "5V_5V") (pintype "bidirectional"))
    )
    (net (code "91") (name "unconnected-(B1-PadA0)") (class "Default")
      (node (ref "B1") (pin "A0") (pinfunction "A0_A0") (pintype "bidirectional"))
    )
    (net (code "92") (name "unconnected-(B1-PadA1)") (class "Default")
      (node (ref "B1") (pin "A1") (pinfunction "A1_A1") (pintype "bidirectional"))
    )
    (net (code "93") (name "unconnected-(B1-PadA2)") (class "Default")
      (node (ref "B1") (pin "A2") (pinfunction "A2_A2") (pintype "bidirectional"))
    )
    (net (code "94") (name "unconnected-(B1-PadA3)") (class "Default")
      (node (ref "B1") (pin "A3") (pinfunction "A3_A3") (pintype "bidirectional"))
    )
    (net (code "95") (name "unconnected-(B1-PadA4)") (class "Default")
      (node (ref "B1") (pin "A4") (pinfunction "A4_A4") (pintype "bidirectional"))
    )
    (net (code "96") (name "unconnected-(B1-PadA5)") (class "Default")
      (node (ref "B1") (pin "A5") (pinfunction "A5_A5") (pintype "bidirectional"))
    )
    (net (code "97") (name "unconnected-(B1-PadAREF)") (class "Default")
      (node (ref "B1") (pin "AREF") (pinfunction "AREF_AREF") (pintype "bidirectional"))
    )
    (net (code "98") (name "unconnected-(B1-PadD0)") (class "Default")
      (node (ref "B1") (pin "D0") (pinfunction "D0_D0") (pintype "bidirectional"))
    )
    (net (code "99") (name "unconnected-(B1-PadD1)") (class "Default")
      (node (ref "B1") (pin "D1") (pinfunction "D1_D1") (pintype "bidirectional"))
    )
    (net (code "100") (name "unconnected-(B1-PadD2)") (class "Default")
      (node (ref "B1") (pin "D2") (pinfunction "D2_D2") (pintype "bidirectional"))
    )
    (net (code "101") (name "unconnected-(B1-PadD4)") (class "Default")
      (node (ref "B1") (pin "D4") (pinfunction "D4_D4") (pintype "bidirectional"))
    )
    (net (code "102") (name "unconnected-(B1-PadD7)") (class "Default")
      (node (ref "B1") (pin "D7") (pinfunction "D7_D7") (pintype "bidirectional"))
    )
    (net (code "103") (name "unconnected-(B1-PadD8)") (class "Default")
      (node (ref "B1") (pin "D8") (pinfunction "D8_D8") (pintype "bidirectional"))
    )
    (net (code "104") (name "unconnected-(B1-PadD12)") (class "Default")
      (node (ref "B1") (pin "D12") (pinfunction "D12_D12") (pintype "bidirectional"))
    )
    (net (code "105") (name "unconnected-(B1-PadD13)") (class "Default")
      (node (ref "B1") (pin "D13") (pinfunction "D13_D13") (pintype "bidirectional"))
    )
    (net (code "106") (name "unconnected-(B1-PadIOREF)") (class "Default")
      (node (ref "B1") (pin "IOREF") (pinfunction "IOREF_IOREF") (pintype "bidirectional"))
    )
    (net (code "107") (name "unconnected-(B1-PadMISO)") (class "Default")
      (node (ref "B1") (pin "MISO") (pinfunction "MISO_MISO") (pintype "bidirectional"))
    )
    (net (code "108") (name "unconnected-(B1-PadMOSI)") (class "Default")
      (node (ref "B1") (pin "MOSI") (pinfunction "MOSI_MOSI") (pintype "bidirectional"))
    )
    (net (code "109") (name "unconnected-(B1-PadSCK)") (class "Default")
      (node (ref "B1") (pin "SCK") (pinfunction "SCK_SCK") (pintype "bidirectional"))
    )
    (net (code "110") (name "unconnected-(B1-PadSCL)") (class "Default")
      (node (ref "B1") (pin "SCL") (pinfunction "SCL_SCL") (pintype "bidirectional"))
    )
    (net (code "111") (name "unconnected-(B1-PadSDA)") (class "Default")
      (node (ref "B1") (pin "SDA") (pinfunction "SDA_SDA") (pintype "bidirectional"))
    )
    (net (code "112") (name "unconnected-(B1-PadVCC)") (class "Default")
      (node (ref "B1") (pin "VCC") (pinfunction "VCC_VCC") (pintype "bidirectional"))
    )
    (net (code "113") (name "unconnected-(B1-PadVIN)") (class "Default")
      (node (ref "B1") (pin "VIN") (pinfunction "VIN_VIN") (pintype "bidirectional"))
    )
    (net (code "114") (name "unconnected-(B1-~{RESET}-PadRESET@1)") (class "Default")
      (node (ref "B1") (pin "RESET@1") (pinfunction "~{RESET}_RESET@1") (pintype "bidirectional"))
    )
    (net (code "115") (name "unconnected-(B1-~{RESET}-PadRESET@2)") (class "Default")
      (node (ref "B1") (pin "RESET@2") (pinfunction "~{RESET}_RESET@2") (pintype "bidirectional"))
    )
    (net (code "116") (name "unconnected-(J4-Pad1)") (class "Default")
      (node (ref "J4") (pin "1") (pinfunction "1_1") (pintype "passive"))
    )
    (net (code "117") (name "unconnected-(J4-Pad2)") (class "Default")
      (node (ref "J4") (pin "2") (pinfunction "2_2") (pintype "passive"))
    )
    (net (code "118") (name "unconnected-(J5-SBU1-PadA8)") (class "Default")
      (node (ref "J5") (pin "A8") (pinfunction "SBU1_A8") (pintype "bidirectional"))
    )
    (net (code "119") (name "unconnected-(J5-SBU2-PadB8)") (class "Default")
      (node (ref "J5") (pin "B8") (pinfunction "SBU2_B8") (pintype "bidirectional"))
    )
    (net (code "120") (name "unconnected-(TVS1-IO2-Pad3)") (class "Default")
      (node (ref "TVS1") (pin "3") (pinfunction "IO2_3") (pintype "passive"))
    )
    (net (code "121") (name "unconnected-(TVS1-IO4-Pad6)") (class "Default")
      (node (ref "TVS1") (pin "6") (pinfunction "IO4_6") (pintype "passive"))
    )
    (net (code "122") (name "unconnected-(U1-CLK-Pad20)") (class "Default")
      (node (ref "U1") (pin "20") (pinfunction "CLK_20") (pintype "bidirectional"))
    )
    (net (code "123") (name "unconnected-(U1-CMD-Pad19)") (class "Default")
      (node (ref "U1") (pin "19") (pinfunction "CMD_19") (pintype "bidirectional"))
    )
    (net (code "124") (name "unconnected-(U1-IO2-Pad24)") (class "Default")
      (node (ref "U1") (pin "24") (pinfunction "IO2_24") (pintype "bidirectional"))
    )
    (net (code "125") (name "unconnected-(U1-IO4-Pad26)") (class "Default")
      (node (ref "U1") (pin "26") (pinfunction "IO4_26") (pintype "bidirectional"))
    )
    (net (code "126") (name "unconnected-(U1-IO12-Pad14)") (class "Default")
      (node (ref "U1") (pin "14") (pinfunction "IO12_14") (pintype "bidirectional"))
    )
    (net (code "127") (name "unconnected-(U1-IO13-Pad16)") (class "Default")
      (node (ref "U1") (pin "16") (pinfunction "IO13_16") (pintype "bidirectional"))
    )
    (net (code "128") (name "unconnected-(U1-IO15-Pad23)") (class "Default")
      (node (ref "U1") (pin "23") (pinfunction "IO15_23") (pintype "bidirectional"))
    )
    (net (code "129") (name "unconnected-(U1-IO16-Pad27)") (class "Default")
      (node (ref "U1") (pin "27") (pinfunction "IO16_27") (pintype "bidirectional"))
    )
    (net (code "130") (name "unconnected-(U1-IO17-Pad28)") (class "Default")
      (node (ref "U1") (pin "28") (pinfunction "IO17_28") (pintype "bidirectional"))
    )
    (net (code "131") (name "unconnected-(U1-IO19-Pad31)") (class "Default")
      (node (ref "U1") (pin "31") (pinfunction "IO19_31") (pintype "bidirectional"))
    )
    (net (code "132") (name "unconnected-(U1-IO32-Pad8)") (class "Default")
      (node (ref "U1") (pin "8") (pinfunction "IO32_8") (pintype "bidirectional"))
    )
    (net (code "133") (name "unconnected-(U1-IO34-Pad6)") (class "Default")
      (node (ref "U1") (pin "6") (pinfunction "IO34_6") (pintype "bidirectional"))
    )
    (net (code "134") (name "unconnected-(U1-IO35-Pad7)") (class "Default")
      (node (ref "U1") (pin "7") (pinfunction "IO35_7") (pintype "bidirectional"))
    )
    (net (code "135") (name "unconnected-(U1-SD0-Pad21)") (class "Default")
      (node (ref "U1") (pin "21") (pinfunction "SD0_21") (pintype "bidirectional"))
    )
    (net (code "136") (name "unconnected-(U1-SD1-Pad22)") (class "Default")
      (node (ref "U1") (pin "22") (pinfunction "SD1_22") (pintype "bidirectional"))
    )
    (net (code "137") (name "unconnected-(U1-SD2-Pad17)") (class "Default")
      (node (ref "U1") (pin "17") (pinfunction "SD2_17") (pintype "bidirectional"))
    )
    (net (code "138") (name "unconnected-(U1-SD3-Pad18)") (class "Default")
      (node (ref "U1") (pin "18") (pinfunction "SD3_18") (pintype "bidirectional"))
    )
    (net (code "139") (name "unconnected-(U1-SVN-Pad5)") (class "Default")
      (node (ref "U1") (pin "5") (pinfunction "SVN_5") (pintype "bidirectional"))
    )
    (net (code "140") (name "unconnected-(U1-SVP-Pad4)") (class "Default")
      (node (ref "U1") (pin "4") (pinfunction "SVP_4") (pintype "bidirectional"))
    )
    (net (code "141") (name "unconnected-(U4-PA02-Pad18)") (class "Default")
      (node (ref "U4") (pin "18") (pinfunction "PA02_18") (pintype "bidirectional"))
    )
    (net (code "142") (name "unconnected-(U4-PA03-Pad19)") (class "Default")
      (node (ref "U4") (pin "19") (pinfunction "PA03_19") (pintype "bidirectional"))
    )
    (net (code "143") (name "unconnected-(U4-PA04-Pad20)") (class "Default")
      (node (ref "U4") (pin "20") (pinfunction "PA04_20") (pintype "bidirectional"))
    )
    (net (code "144") (name "unconnected-(U4-PA05-Pad1)") (class "Default")
      (node (ref "U4") (pin "1") (pinfunction "PA05_1") (pintype "bidirectional"))
    )
    (net (code "145") (name "unconnected-(U4-PA06-Pad2)") (class "Default")
      (node (ref "U4") (pin "2") (pinfunction "PA06_2") (pintype "bidirectional"))
    )
    (net (code "146") (name "unconnected-(U4-PA07-Pad3)") (class "Default")
      (node (ref "U4") (pin "3") (pinfunction "PA07_3") (pintype "bidirectional"))
    )
    (net (code "147") (name "unconnected-(U4-PA08{slash}XIN32-Pad4)") (class "Default")
      (node (ref "U4") (pin "4") (pinfunction "PA08/XIN32_4") (pintype "input"))
    )
    (net (code "148") (name "unconnected-(U4-PA09{slash}XOUT32-Pad5)") (class "Default")
      (node (ref "U4") (pin "5") (pinfunction "PA09/XOUT32_5") (pintype "input"))
    )
    (net (code "149") (name "unconnected-(U4-PA16-Pad8)") (class "Default")
      (node (ref "U4") (pin "8") (pinfunction "PA16_8") (pintype "bidirectional"))
    )
    (net (code "150") (name "unconnected-(U6-4A-Pad9)") (class "Default")
      (node (ref "U6") (pin "9") (pinfunction "4A_9") (pintype "bidirectional"))
    )
    (net (code "151") (name "unconnected-(U6-4Y-Pad10)") (class "Default")
      (node (ref "U6") (pin "10") (pinfunction "4Y_10") (pintype "bidirectional"))
    )
  )
)
